# TPS54531.net
KiCad netlist of a schematic drawn in Altium Designer
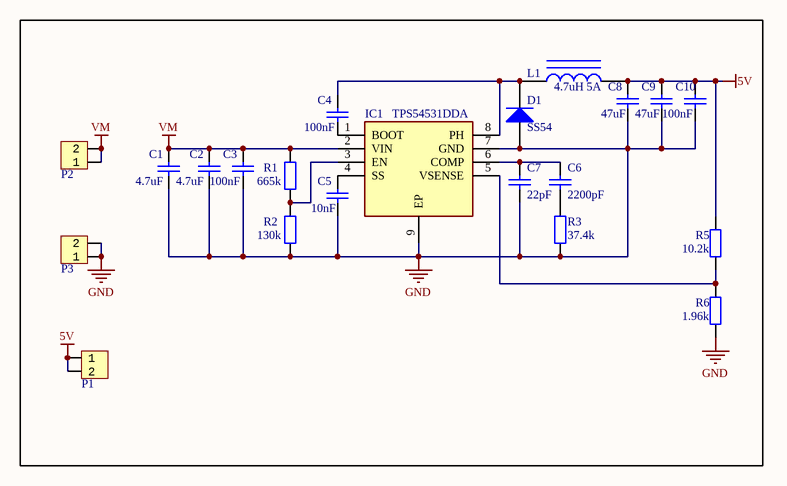
[diagram p0: TPS54531.SchDoc]

(export (version "E")
  (design (tool "Eeschema 10.0.6"))
  (components
    (comp (ref "C1")
      (value "4.7uF")
      (footprint "CAP-0603")
      (description "贴片电容")
      (libsource (lib "Power_Lib_Altium") (part "CAP"))
    )
    (comp (ref "C2")
      (value "4.7uF")
      (footprint "CAP-0603")
      (description "贴片电容")
      (libsource (lib "Power_Lib_Altium") (part "CAP"))
    )
    (comp (ref "C3")
      (value "100nF")
      (footprint "CAP-0603")
      (description "贴片电容")
      (libsource (lib "Power_Lib_Altium") (part "CAP"))
    )
    (comp (ref "C4")
      (value "100nF")
      (footprint "CAP-0603")
      (description "贴片电容")
      (libsource (lib "Power_Lib_Altium") (part "CAP"))
    )
    (comp (ref "C5")
      (value "10nF")
      (footprint "CAP-0603")
      (description "贴片电容")
      (libsource (lib "Power_Lib_Altium") (part "CAP"))
    )
    (comp (ref "C6")
      (value "2200pF")
      (footprint "CAP-0603")
      (description "贴片电容")
      (libsource (lib "Power_Lib_Altium") (part "CAP"))
    )
    (comp (ref "C7")
      (value "22pF")
      (footprint "CAP-0603")
      (description "贴片电容")
      (libsource (lib "Power_Lib_Altium") (part "CAP"))
    )
    (comp (ref "C8")
      (value "47uF")
      (footprint "CAP-0603")
      (description "贴片电容")
      (libsource (lib "Power_Lib_Altium") (part "CAP"))
    )
    (comp (ref "C9")
      (value "47uF")
      (footprint "CAP-0603")
      (description "贴片电容")
      (libsource (lib "Power_Lib_Altium") (part "CAP"))
    )
    (comp (ref "C10")
      (value "100nF")
      (footprint "CAP-0603")
      (description "贴片电容")
      (libsource (lib "Power_Lib_Altium") (part "CAP"))
    )
    (comp (ref "D1")
      (value "SS54")
      (footprint "DO-214AB")
      (description "肖特基二极管")
      (libsource (lib "Power_Lib_Altium") (part "DIODE"))
    )
    (comp (ref "IC1")
      (value "TPS54531DDA")
      (footprint "SOIC_8_PAD")
      (description "集成稳压芯片")
      (fields (field (name "MOUSER PART NUMBER") "595-TPS54531DDA"))
      (libsource (lib "Power_Lib_Altium") (part "TPS54531DDA"))
    )
    (comp (ref "L1")
      (value "4.7uH 5A")
      (footprint "L-10040")
      (description "电感")
      (libsource (lib "Power_Lib_Altium") (part "INDUCTOR"))
    )
    (comp (ref "P1")
      (value "HDR1x2_2.54")
      (footprint "HDR1X2_2.54_180")
      (description "Header")
      (libsource (lib "") (part "HDR1x2_2.54_1"))
    )
    (comp (ref "P2")
      (value "HDR1x2_2.54")
      (footprint "HDR1X2_2.54_180")
      (description "Header")
      (libsource (lib "Power_Lib_Altium") (part "HDR1x2_2.54"))
    )
    (comp (ref "P3")
      (value "HDR1x2_2.54")
      (footprint "HDR1X2_2.54_180")
      (description "Header")
      (libsource (lib "Power_Lib_Altium") (part "HDR1x2_2.54"))
    )
    (comp (ref "R1")
      (value "665k")
      (footprint "R-0603")
      (description "贴片电阻")
      (libsource (lib "Power_Lib_Altium") (part "RES"))
    )
    (comp (ref "R2")
      (value "130k")
      (footprint "R-0603")
      (description "贴片电阻")
      (libsource (lib "Power_Lib_Altium") (part "RES"))
    )
    (comp (ref "R3")
      (value "37.4k")
      (footprint "R-0603")
      (description "贴片电阻")
      (libsource (lib "Power_Lib_Altium") (part "RES"))
    )
    (comp (ref "R5")
      (value "10.2k")
      (footprint "R-0603")
      (description "贴片电阻")
      (libsource (lib "Power_Lib_Altium") (part "RES"))
    )
    (comp (ref "R6")
      (value "1.96k")
      (footprint "R-0603")
      (description "贴片电阻")
      (libsource (lib "Power_Lib_Altium") (part "RES"))
    )
  )
  (nets
    (net (code "1") (name "5V") (class "Default")
      (node (ref "C10") (pin "2") (pinfunction "2_2") (pintype "passive"))
      (node (ref "C8") (pin "2") (pinfunction "2_2") (pintype "passive"))
      (node (ref "C9") (pin "2") (pinfunction "2_2") (pintype "passive"))
      (node (ref "L1") (pin "2") (pinfunction "2_2") (pintype "passive"))
      (node (ref "P1") (pin "1") (pinfunction "1_1") (pintype "passive"))
      (node (ref "P1") (pin "2") (pinfunction "2_2") (pintype "passive"))
      (node (ref "R5") (pin "2") (pinfunction "2_2") (pintype "passive"))
    )
    (net (code "2") (name "GND") (class "Default")
      (node (ref "C1") (pin "1") (pinfunction "1_1") (pintype "passive"))
      (node (ref "C10") (pin "1") (pinfunction "1_1") (pintype "passive"))
      (node (ref "C2") (pin "1") (pinfunction "1_1") (pintype "passive"))
      (node (ref "C3") (pin "1") (pinfunction "1_1") (pintype "passive"))
      (node (ref "C5") (pin "1") (pinfunction "1_1") (pintype "passive"))
      (node (ref "C7") (pin "1") (pinfunction "1_1") (pintype "passive"))
      (node (ref "C8") (pin "1") (pinfunction "1_1") (pintype "passive"))
      (node (ref "C9") (pin "1") (pinfunction "1_1") (pintype "passive"))
      (node (ref "D1") (pin "1") (pinfunction "A_1") (pintype "passive"))
      (node (ref "IC1") (pin "7") (pinfunction "GND_7") (pintype "passive"))
      (node (ref "IC1") (pin "9") (pinfunction "EP_9") (pintype "passive"))
      (node (ref "P3") (pin "1") (pinfunction "1_1") (pintype "passive"))
      (node (ref "P3") (pin "2") (pinfunction "2_2") (pintype "passive"))
      (node (ref "R2") (pin "1") (pinfunction "1_1") (pintype "passive"))
      (node (ref "R3") (pin "1") (pinfunction "1_1") (pintype "passive"))
      (node (ref "R6") (pin "1") (pinfunction "1_1") (pintype "passive"))
    )
    (net (code "3") (name "Net-(C6-Pad1)") (class "Default")
      (node (ref "C6") (pin "1") (pinfunction "1_1") (pintype "passive"))
      (node (ref "R3") (pin "2") (pinfunction "2_2") (pintype "passive"))
    )
    (net (code "4") (name "Net-(D1-K)") (class "Default")
      (node (ref "C4") (pin "2") (pinfunction "2_2") (pintype "passive"))
      (node (ref "D1") (pin "2") (pinfunction "K_2") (pintype "passive"))
      (node (ref "IC1") (pin "8") (pinfunction "PH_8") (pintype "passive"))
      (node (ref "L1") (pin "1") (pinfunction "1_1") (pintype "passive"))
    )
    (net (code "5") (name "Net-(IC1-BOOT)") (class "Default")
      (node (ref "C4") (pin "1") (pinfunction "1_1") (pintype "passive"))
      (node (ref "IC1") (pin "1") (pinfunction "BOOT_1") (pintype "passive"))
    )
    (net (code "6") (name "Net-(IC1-COMP)") (class "Default")
      (node (ref "C6") (pin "2") (pinfunction "2_2") (pintype "passive"))
      (node (ref "C7") (pin "2") (pinfunction "2_2") (pintype "passive"))
      (node (ref "IC1") (pin "6") (pinfunction "COMP_6") (pintype "passive"))
    )
    (net (code "7") (name "Net-(IC1-EN)") (class "Default")
      (node (ref "IC1") (pin "3") (pinfunction "EN_3") (pintype "passive"))
      (node (ref "R1") (pin "1") (pinfunction "1_1") (pintype "passive"))
      (node (ref "R2") (pin "2") (pinfunction "2_2") (pintype "passive"))
    )
    (net (code "8") (name "Net-(IC1-SS)") (class "Default")
      (node (ref "C5") (pin "2") (pinfunction "2_2") (pintype "passive"))
      (node (ref "IC1") (pin "4") (pinfunction "SS_4") (pintype "passive"))
    )
    (net (code "9") (name "Net-(IC1-VSENSE)") (class "Default")
      (node (ref "IC1") (pin "5") (pinfunction "VSENSE_5") (pintype "passive"))
      (node (ref "R5") (pin "1") (pinfunction "1_1") (pintype "passive"))
      (node (ref "R6") (pin "2") (pinfunction "2_2") (pintype "passive"))
    )
    (net (code "10") (name "VM") (class "Default")
      (node (ref "C1") (pin "2") (pinfunction "2_2") (pintype "passive"))
      (node (ref "C2") (pin "2") (pinfunction "2_2") (pintype "passive"))
      (node (ref "C3") (pin "2") (pinfunction "2_2") (pintype "passive"))
      (node (ref "IC1") (pin "2") (pinfunction "VIN_2") (pintype "passive"))
      (node (ref "P2") (pin "1") (pinfunction "1_1") (pintype "passive"))
      (node (ref "P2") (pin "2") (pinfunction "2_2") (pintype "passive"))
      (node (ref "R1") (pin "2") (pinfunction "2_2") (pintype "passive"))
    )
  )
)
